# Kill_Switch.net
KiCad netlist of a schematic drawn in Altium Designer
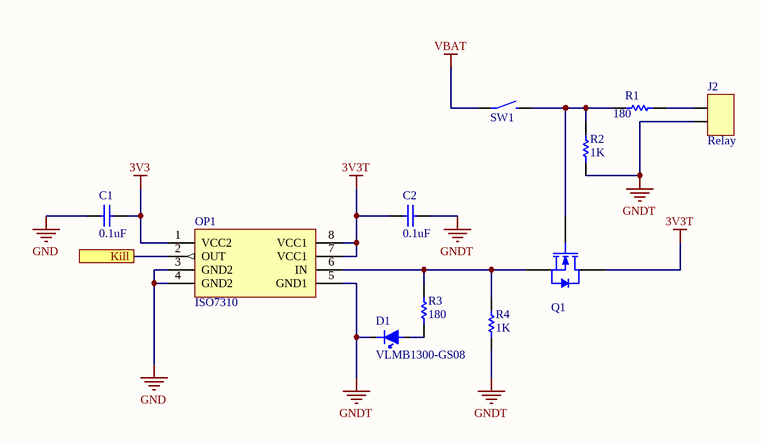
[diagram p0: Kill_Switch.SchDoc]

(export (version "E")
  (design (tool "Eeschema 10.0.6"))
  (components
    (comp (ref "C1")
      (value "0.1uF")
      (footprint "CAPC1608X97X38NL12T08")
      (description "CAP CER 0.1UF 25V X7R 0603")
      (fields (field (name "MANUFACTURER") "Vitramon") (field (name "PART NUMBER") "VJ0603Y-104KXXAC"))
      (libsource (lib "Main") (part "VJ0603Y104KXXAC"))
    )
    (comp (ref "C2")
      (value "0.1uF")
      (footprint "CAPC1608X97X38NL12T08")
      (description "CAP CER 0.1UF 25V X7R 0603")
      (fields (field (name "MANUFACTURER") "Vitramon") (field (name "PART NUMBER") "VJ0603Y-104KXXAC"))
      (libsource (lib "Main") (part "VJ0603Y104KXXAC"))
    )
    (comp (ref "D1")
      (value "VLMB1300-GS08")
      (footprint "0603 - DIODE")
      (description "Blue 470nm LED Indication - Discrete 3.3V 0603 (1608 Metric)")
      (libsource (lib "Main") (part "VLMB1300-GS08"))
    )
    (comp (ref "J2") (value "Relay") (footprint "2PinHeader") (libsource (lib "Main") (part "2PinHeader")))
    (comp (ref "OP1")
      (value "ISO7310")
      (footprint "ISO7310CDR - 8 SOIC")
      (libsource (lib "Main") (part "ISO7310CDR - 8SOIC"))
    )
    (comp (ref "Q1")
      (value "MOSFET N-CH")
      (footprint "ONSC-SOT-23-3-318-08_V")
      (description "MOSFET N-CH 50V 200MA SOT-23")
      (libsource (lib "Main") (part "BSS138LT1G"))
    )
    (comp (ref "R1")
      (value "180")
      (footprint "RESC1609X55X30NL10T20")
      (description "RES 180 OHM 0.1% 1/8W 0603")
      (fields (field (name "TOLERANCE") "1%"))
      (libsource (lib "Main") (part "TNPW0603180RBEEA"))
    )
    (comp (ref "R2")
      (value "1K")
      (footprint "RESC1609X55X30NL10T20")
      (description "RES 1K OHM 0.1% 1/8W 0603")
      (fields (field (name "TOLERANCE") "1%"))
      (libsource (lib "Main") (part "TNPW06031K00BEEA"))
    )
    (comp (ref "R3")
      (value "180")
      (footprint "RESC1609X55X30NL10T20")
      (description "RES 180 OHM 0.1% 1/8W 0603")
      (fields (field (name "TOLERANCE") "1%"))
      (libsource (lib "Main") (part "TNPW0603180RBEEA"))
    )
    (comp (ref "R4")
      (value "1K")
      (footprint "RESC1609X55X30NL10T20")
      (description "RES 1K OHM 0.1% 1/8W 0603")
      (fields (field (name "TOLERANCE") "1%"))
      (libsource (lib "Main") (part "TNPW06031K00BEEA"))
    )
    (comp (ref "SW1")
      (value "SwitchHeader")
      (footprint "2PinHeader")
      (libsource (lib "Main") (part "SwitchHeader"))
    )
  )
  (nets
    (net (code "1") (name "/Kill") (class "Default")
      (node (ref "OP1") (pin "2") (pinfunction "OUT_2") (pintype "output"))
    )
    (net (code "2") (name "3V3") (class "Default")
      (node (ref "C1") (pin "1") (pinfunction "1_1") (pintype "passive"))
      (node (ref "OP1") (pin "1") (pinfunction "VCC2_1") (pintype "power_in"))
    )
    (net (code "3") (name "3V3T") (class "Default")
      (node (ref "C2") (pin "1") (pinfunction "1_1") (pintype "passive"))
      (node (ref "OP1") (pin "7") (pinfunction "VCC1_7") (pintype "power_in"))
      (node (ref "OP1") (pin "8") (pinfunction "VCC1_8") (pintype "power_in"))
      (node (ref "Q1") (pin "3") (pinfunction "D_3") (pintype "passive"))
    )
    (net (code "4") (name "GND") (class "Default")
      (node (ref "C1") (pin "2") (pinfunction "2_2") (pintype "passive"))
      (node (ref "OP1") (pin "3") (pinfunction "GND2_3") (pintype "passive"))
      (node (ref "OP1") (pin "4") (pinfunction "GND2_4") (pintype "passive"))
    )
    (net (code "5") (name "GNDT") (class "Default")
      (node (ref "C2") (pin "2") (pinfunction "2_2") (pintype "passive"))
      (node (ref "D1") (pin "C") (pinfunction "C_C") (pintype "passive"))
      (node (ref "J2") (pin "2") (pintype "passive"))
      (node (ref "OP1") (pin "5") (pinfunction "GND1_5") (pintype "passive"))
      (node (ref "R2") (pin "1") (pinfunction "1_1") (pintype "passive"))
      (node (ref "R4") (pin "1") (pinfunction "1_1") (pintype "passive"))
    )
    (net (code "6") (name "Net-(D1-PadA)") (class "Default")
      (node (ref "D1") (pin "A") (pinfunction "A_A") (pintype "passive"))
      (node (ref "R3") (pin "1") (pinfunction "1_1") (pintype "passive"))
    )
    (net (code "7") (name "Net-(J2-Pad1)") (class "Default")
      (node (ref "J2") (pin "1") (pintype "passive"))
      (node (ref "R1") (pin "2") (pinfunction "2_2") (pintype "passive"))
    )
    (net (code "8") (name "Net-(OP1-IN)") (class "Default")
      (node (ref "OP1") (pin "6") (pinfunction "IN_6") (pintype "tri_state"))
      (node (ref "Q1") (pin "2") (pinfunction "S_2") (pintype "passive"))
      (node (ref "R3") (pin "2") (pinfunction "2_2") (pintype "passive"))
      (node (ref "R4") (pin "2") (pinfunction "2_2") (pintype "passive"))
    )
    (net (code "9") (name "Net-(Q1-G)") (class "Default")
      (node (ref "Q1") (pin "1") (pinfunction "G_1") (pintype "passive"))
      (node (ref "R1") (pin "1") (pinfunction "1_1") (pintype "passive"))
      (node (ref "R2") (pin "2") (pinfunction "2_2") (pintype "passive"))
      (node (ref "SW1") (pin "2") (pinfunction "2_2") (pintype "passive"))
    )
    (net (code "10") (name "VBAT") (class "Default")
      (node (ref "SW1") (pin "1") (pinfunction "1_1") (pintype "passive"))
    )
  )
)
